# Atari_ST_4MB_RAM.net
KiCad netlist of a schematic drawn in EAGLE
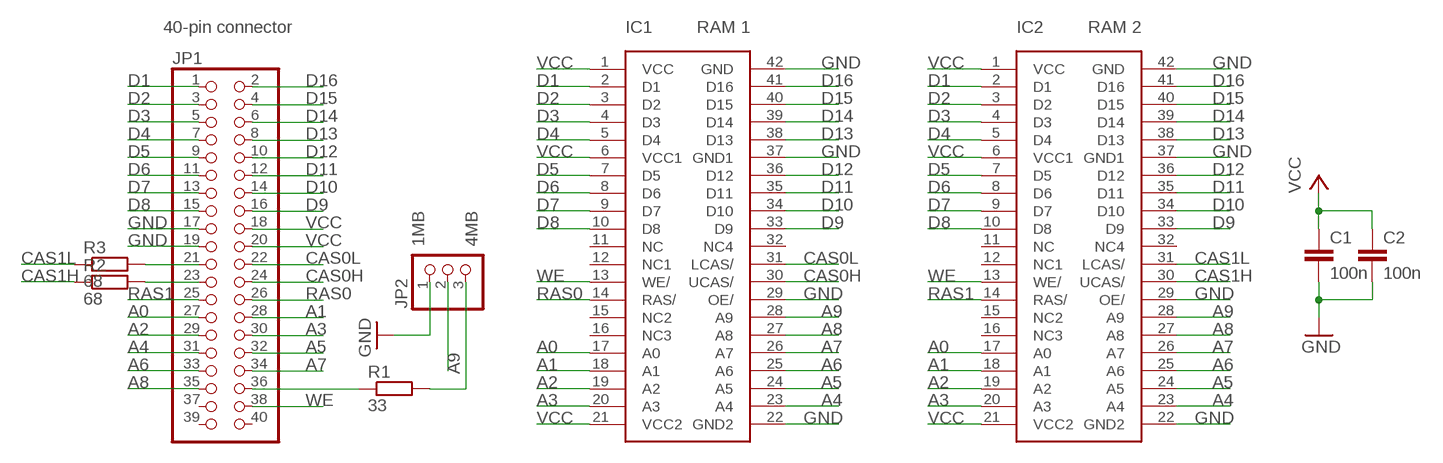
[diagram p0: schematic, sheet 1]

(export (version "E")
  (design (tool "Eeschema 10.0.6"))
  (components
    (comp (ref "C1")
      (value "100n")
      (footprint "eagle-import:C0805")
      (libsource (lib "eagle-import") (part "C-EUC0805"))
    )
    (comp (ref "C2")
      (value "100n")
      (footprint "eagle-import:C0805")
      (libsource (lib "eagle-import") (part "C-EUC0805"))
    )
    (comp (ref "IC1")
      (value "DRAMSOJ40A")
      (footprint "eagle-import:SOJ40")
      (libsource (lib "eagle-import") (part "DRAMSOJ40A"))
    )
    (comp (ref "IC2")
      (value "DRAMSOJ40A")
      (footprint "eagle-import:SOJ40")
      (libsource (lib "eagle-import") (part "DRAMSOJ40A"))
    )
    (comp (ref "JP1")
      (value "PINHD-2X20")
      (footprint "eagle-import:2X20")
      (libsource (lib "eagle-import") (part "PINHD-2X20"))
    )
    (comp (ref "JP2")
      (value "PINHD-1X3")
      (footprint "eagle-import:1X03")
      (libsource (lib "eagle-import") (part "PINHD-1X3"))
    )
    (comp (ref "R1")
      (value "33")
      (footprint "eagle-import:R0805")
      (libsource (lib "eagle-import") (part "R-EU_R0805"))
    )
    (comp (ref "R2")
      (value "68")
      (footprint "eagle-import:R0805")
      (libsource (lib "eagle-import") (part "R-EU_R0805"))
    )
    (comp (ref "R3")
      (value "68")
      (footprint "eagle-import:R0805")
      (libsource (lib "eagle-import") (part "R-EU_R0805"))
    )
  )
  (nets
    (net (code "1") (name "/A0") (class "Default")
      (node (ref "IC1") (pin "17") (pinfunction "A0_17") (pintype "input"))
      (node (ref "IC2") (pin "17") (pinfunction "A0_17") (pintype "input"))
      (node (ref "JP1") (pin "27") (pinfunction "27_27") (pintype "passive"))
    )
    (net (code "2") (name "/A1") (class "Default")
      (node (ref "IC1") (pin "18") (pinfunction "A1_18") (pintype "input"))
      (node (ref "IC2") (pin "18") (pinfunction "A1_18") (pintype "input"))
      (node (ref "JP1") (pin "28") (pinfunction "28_28") (pintype "passive"))
    )
    (net (code "3") (name "/A2") (class "Default")
      (node (ref "IC1") (pin "19") (pinfunction "A2_19") (pintype "input"))
      (node (ref "IC2") (pin "19") (pinfunction "A2_19") (pintype "input"))
      (node (ref "JP1") (pin "29") (pinfunction "29_29") (pintype "passive"))
    )
    (net (code "4") (name "/A3") (class "Default")
      (node (ref "IC1") (pin "20") (pinfunction "A3_20") (pintype "input"))
      (node (ref "IC2") (pin "20") (pinfunction "A3_20") (pintype "input"))
      (node (ref "JP1") (pin "30") (pinfunction "30_30") (pintype "passive"))
    )
    (net (code "5") (name "/A4") (class "Default")
      (node (ref "IC1") (pin "23") (pinfunction "A4_23") (pintype "input"))
      (node (ref "IC2") (pin "23") (pinfunction "A4_23") (pintype "input"))
      (node (ref "JP1") (pin "31") (pinfunction "31_31") (pintype "passive"))
    )
    (net (code "6") (name "/A5") (class "Default")
      (node (ref "IC1") (pin "24") (pinfunction "A5_24") (pintype "input"))
      (node (ref "IC2") (pin "24") (pinfunction "A5_24") (pintype "input"))
      (node (ref "JP1") (pin "32") (pinfunction "32_32") (pintype "passive"))
    )
    (net (code "7") (name "/A6") (class "Default")
      (node (ref "IC1") (pin "25") (pinfunction "A6_25") (pintype "input"))
      (node (ref "IC2") (pin "25") (pinfunction "A6_25") (pintype "input"))
      (node (ref "JP1") (pin "33") (pinfunction "33_33") (pintype "passive"))
    )
    (net (code "8") (name "/A7") (class "Default")
      (node (ref "IC1") (pin "26") (pinfunction "A7_26") (pintype "input"))
      (node (ref "IC2") (pin "26") (pinfunction "A7_26") (pintype "input"))
      (node (ref "JP1") (pin "34") (pinfunction "34_34") (pintype "passive"))
    )
    (net (code "9") (name "/A8") (class "Default")
      (node (ref "IC1") (pin "27") (pinfunction "A8_27") (pintype "input"))
      (node (ref "IC2") (pin "27") (pinfunction "A8_27") (pintype "input"))
      (node (ref "JP1") (pin "35") (pinfunction "35_35") (pintype "passive"))
    )
    (net (code "10") (name "/A9") (class "Default")
      (node (ref "IC1") (pin "28") (pinfunction "A9_28") (pintype "input"))
      (node (ref "IC2") (pin "28") (pinfunction "A9_28") (pintype "input"))
      (node (ref "JP2") (pin "2") (pinfunction "2_2") (pintype "passive"))
    )
    (net (code "11") (name "/CAS0H") (class "Default")
      (node (ref "IC1") (pin "30") (pinfunction "UCAS/_30") (pintype "bidirectional"))
      (node (ref "JP1") (pin "24") (pinfunction "24_24") (pintype "passive"))
    )
    (net (code "12") (name "/CAS0L") (class "Default")
      (node (ref "IC1") (pin "31") (pinfunction "LCAS/_31") (pintype "bidirectional"))
      (node (ref "JP1") (pin "22") (pinfunction "22_22") (pintype "passive"))
    )
    (net (code "13") (name "/CAS1H") (class "Default")
      (node (ref "IC2") (pin "30") (pinfunction "UCAS/_30") (pintype "bidirectional"))
      (node (ref "R2") (pin "1") (pinfunction "1_1") (pintype "passive"))
    )
    (net (code "14") (name "/CAS1L") (class "Default")
      (node (ref "IC2") (pin "31") (pinfunction "LCAS/_31") (pintype "bidirectional"))
      (node (ref "R3") (pin "1") (pinfunction "1_1") (pintype "passive"))
    )
    (net (code "15") (name "/D1") (class "Default")
      (node (ref "IC1") (pin "2") (pinfunction "D1_2") (pintype "tri_state"))
      (node (ref "IC2") (pin "2") (pinfunction "D1_2") (pintype "tri_state"))
      (node (ref "JP1") (pin "1") (pinfunction "1_1") (pintype "passive"))
    )
    (net (code "16") (name "/D2") (class "Default")
      (node (ref "IC1") (pin "3") (pinfunction "D2_3") (pintype "tri_state"))
      (node (ref "IC2") (pin "3") (pinfunction "D2_3") (pintype "tri_state"))
      (node (ref "JP1") (pin "3") (pinfunction "3_3") (pintype "passive"))
    )
    (net (code "17") (name "/D3") (class "Default")
      (node (ref "IC1") (pin "4") (pinfunction "D3_4") (pintype "tri_state"))
      (node (ref "IC2") (pin "4") (pinfunction "D3_4") (pintype "tri_state"))
      (node (ref "JP1") (pin "5") (pinfunction "5_5") (pintype "passive"))
    )
    (net (code "18") (name "/D4") (class "Default")
      (node (ref "IC1") (pin "5") (pinfunction "D4_5") (pintype "tri_state"))
      (node (ref "IC2") (pin "5") (pinfunction "D4_5") (pintype "tri_state"))
      (node (ref "JP1") (pin "7") (pinfunction "7_7") (pintype "passive"))
    )
    (net (code "19") (name "/D5") (class "Default")
      (node (ref "IC1") (pin "7") (pinfunction "D5_7") (pintype "tri_state"))
      (node (ref "IC2") (pin "7") (pinfunction "D5_7") (pintype "tri_state"))
      (node (ref "JP1") (pin "9") (pinfunction "9_9") (pintype "passive"))
    )
    (net (code "20") (name "/D6") (class "Default")
      (node (ref "IC1") (pin "8") (pinfunction "D6_8") (pintype "tri_state"))
      (node (ref "IC2") (pin "8") (pinfunction "D6_8") (pintype "tri_state"))
      (node (ref "JP1") (pin "11") (pinfunction "11_11") (pintype "passive"))
    )
    (net (code "21") (name "/D7") (class "Default")
      (node (ref "IC1") (pin "9") (pinfunction "D7_9") (pintype "tri_state"))
      (node (ref "IC2") (pin "9") (pinfunction "D7_9") (pintype "tri_state"))
      (node (ref "JP1") (pin "13") (pinfunction "13_13") (pintype "passive"))
    )
    (net (code "22") (name "/D8") (class "Default")
      (node (ref "IC1") (pin "10") (pinfunction "D8_10") (pintype "tri_state"))
      (node (ref "IC2") (pin "10") (pinfunction "D8_10") (pintype "tri_state"))
      (node (ref "JP1") (pin "15") (pinfunction "15_15") (pintype "passive"))
    )
    (net (code "23") (name "/D9") (class "Default")
      (node (ref "IC1") (pin "33") (pinfunction "D9_33") (pintype "input"))
      (node (ref "IC2") (pin "33") (pinfunction "D9_33") (pintype "input"))
      (node (ref "JP1") (pin "16") (pinfunction "16_16") (pintype "passive"))
    )
    (net (code "24") (name "/D10") (class "Default")
      (node (ref "IC1") (pin "34") (pinfunction "D10_34") (pintype "input"))
      (node (ref "IC2") (pin "34") (pinfunction "D10_34") (pintype "input"))
      (node (ref "JP1") (pin "14") (pinfunction "14_14") (pintype "passive"))
    )
    (net (code "25") (name "/D11") (class "Default")
      (node (ref "IC1") (pin "35") (pinfunction "D11_35") (pintype "input"))
      (node (ref "IC2") (pin "35") (pinfunction "D11_35") (pintype "input"))
      (node (ref "JP1") (pin "12") (pinfunction "12_12") (pintype "passive"))
    )
    (net (code "26") (name "/D12") (class "Default")
      (node (ref "IC1") (pin "36") (pinfunction "D12_36") (pintype "input"))
      (node (ref "IC2") (pin "36") (pinfunction "D12_36") (pintype "input"))
      (node (ref "JP1") (pin "10") (pinfunction "10_10") (pintype "passive"))
    )
    (net (code "27") (name "/D13") (class "Default")
      (node (ref "IC1") (pin "38") (pinfunction "D13_38") (pintype "input"))
      (node (ref "IC2") (pin "38") (pinfunction "D13_38") (pintype "input"))
      (node (ref "JP1") (pin "8") (pinfunction "8_8") (pintype "passive"))
    )
    (net (code "28") (name "/D14") (class "Default")
      (node (ref "IC1") (pin "39") (pinfunction "D14_39") (pintype "input"))
      (node (ref "IC2") (pin "39") (pinfunction "D14_39") (pintype "input"))
      (node (ref "JP1") (pin "6") (pinfunction "6_6") (pintype "passive"))
    )
    (net (code "29") (name "/D15") (class "Default")
      (node (ref "IC1") (pin "40") (pinfunction "D15_40") (pintype "input"))
      (node (ref "IC2") (pin "40") (pinfunction "D15_40") (pintype "input"))
      (node (ref "JP1") (pin "4") (pinfunction "4_4") (pintype "passive"))
    )
    (net (code "30") (name "/D16") (class "Default")
      (node (ref "IC1") (pin "41") (pinfunction "D16_41") (pintype "input"))
      (node (ref "IC2") (pin "41") (pinfunction "D16_41") (pintype "input"))
      (node (ref "JP1") (pin "2") (pinfunction "2_2") (pintype "passive"))
    )
    (net (code "31") (name "/RAS0") (class "Default")
      (node (ref "IC1") (pin "14") (pinfunction "RAS/_14") (pintype "input"))
      (node (ref "JP1") (pin "26") (pinfunction "26_26") (pintype "passive"))
    )
    (net (code "32") (name "/RAS1") (class "Default")
      (node (ref "IC2") (pin "14") (pinfunction "RAS/_14") (pintype "input"))
      (node (ref "JP1") (pin "25") (pinfunction "25_25") (pintype "passive"))
    )
    (net (code "33") (name "/WE") (class "Default")
      (node (ref "IC1") (pin "13") (pinfunction "WE/_13") (pintype "input"))
      (node (ref "IC2") (pin "13") (pinfunction "WE/_13") (pintype "input"))
      (node (ref "JP1") (pin "38") (pinfunction "38_38") (pintype "passive"))
    )
    (net (code "34") (name "GND") (class "Default")
      (node (ref "C1") (pin "2") (pinfunction "2_2") (pintype "passive"))
      (node (ref "C2") (pin "2") (pinfunction "2_2") (pintype "passive"))
      (node (ref "IC1") (pin "22") (pinfunction "GND2_22") (pintype "power_in"))
      (node (ref "IC1") (pin "29") (pinfunction "OE/_29") (pintype "input"))
      (node (ref "IC1") (pin "37") (pinfunction "GND1_37") (pintype "power_in"))
      (node (ref "IC1") (pin "42") (pinfunction "GND_42") (pintype "power_in"))
      (node (ref "IC2") (pin "22") (pinfunction "GND2_22") (pintype "power_in"))
      (node (ref "IC2") (pin "29") (pinfunction "OE/_29") (pintype "input"))
      (node (ref "IC2") (pin "37") (pinfunction "GND1_37") (pintype "power_in"))
      (node (ref "IC2") (pin "42") (pinfunction "GND_42") (pintype "power_in"))
      (node (ref "JP1") (pin "17") (pinfunction "17_17") (pintype "passive"))
      (node (ref "JP1") (pin "19") (pinfunction "19_19") (pintype "passive"))
      (node (ref "JP2") (pin "1") (pinfunction "1_1") (pintype "passive"))
    )
    (net (code "35") (name "Net-(JP1-Pad21)") (class "Default")
      (node (ref "JP1") (pin "21") (pinfunction "21_21") (pintype "passive"))
      (node (ref "R3") (pin "2") (pinfunction "2_2") (pintype "passive"))
    )
    (net (code "36") (name "Net-(JP1-Pad23)") (class "Default")
      (node (ref "JP1") (pin "23") (pinfunction "23_23") (pintype "passive"))
      (node (ref "R2") (pin "2") (pinfunction "2_2") (pintype "passive"))
    )
    (net (code "37") (name "Net-(JP1-Pad36)") (class "Default")
      (node (ref "JP1") (pin "36") (pinfunction "36_36") (pintype "passive"))
      (node (ref "R1") (pin "1") (pinfunction "1_1") (pintype "passive"))
    )
    (net (code "38") (name "Net-(JP2-Pad3)") (class "Default")
      (node (ref "JP2") (pin "3") (pinfunction "3_3") (pintype "passive"))
      (node (ref "R1") (pin "2") (pinfunction "2_2") (pintype "passive"))
    )
    (net (code "39") (name "VCC") (class "Default")
      (node (ref "C1") (pin "1") (pinfunction "1_1") (pintype "passive"))
      (node (ref "C2") (pin "1") (pinfunction "1_1") (pintype "passive"))
      (node (ref "IC1") (pin "1") (pinfunction "VCC_1") (pintype "power_in"))
      (node (ref "IC1") (pin "21") (pinfunction "VCC2_21") (pintype "power_in"))
      (node (ref "IC1") (pin "6") (pinfunction "VCC1_6") (pintype "power_in"))
      (node (ref "IC2") (pin "1") (pinfunction "VCC_1") (pintype "power_in"))
      (node (ref "IC2") (pin "21") (pinfunction "VCC2_21") (pintype "power_in"))
      (node (ref "IC2") (pin "6") (pinfunction "VCC1_6") (pintype "power_in"))
      (node (ref "JP1") (pin "18") (pinfunction "18_18") (pintype "passive"))
      (node (ref "JP1") (pin "20") (pinfunction "20_20") (pintype "passive"))
    )
    (net (code "40") (name "unconnected-(IC1-NC-Pad11)") (class "Default")
      (node (ref "IC1") (pin "11") (pinfunction "NC_11") (pintype "no_connect"))
    )
    (net (code "41") (name "unconnected-(IC1-NC1-Pad12)") (class "Default")
      (node (ref "IC1") (pin "12") (pinfunction "NC1_12") (pintype "no_connect"))
    )
    (net (code "42") (name "unconnected-(IC1-NC2-Pad15)") (class "Default")
      (node (ref "IC1") (pin "15") (pinfunction "NC2_15") (pintype "no_connect"))
    )
    (net (code "43") (name "unconnected-(IC1-NC3-Pad16)") (class "Default")
      (node (ref "IC1") (pin "16") (pinfunction "NC3_16") (pintype "no_connect"))
    )
    (net (code "44") (name "unconnected-(IC1-NC4-Pad32)") (class "Default")
      (node (ref "IC1") (pin "32") (pinfunction "NC4_32") (pintype "no_connect"))
    )
    (net (code "45") (name "unconnected-(IC2-NC-Pad11)") (class "Default")
      (node (ref "IC2") (pin "11") (pinfunction "NC_11") (pintype "no_connect"))
    )
    (net (code "46") (name "unconnected-(IC2-NC1-Pad12)") (class "Default")
      (node (ref "IC2") (pin "12") (pinfunction "NC1_12") (pintype "no_connect"))
    )
    (net (code "47") (name "unconnected-(IC2-NC2-Pad15)") (class "Default")
      (node (ref "IC2") (pin "15") (pinfunction "NC2_15") (pintype "no_connect"))
    )
    (net (code "48") (name "unconnected-(IC2-NC3-Pad16)") (class "Default")
      (node (ref "IC2") (pin "16") (pinfunction "NC3_16") (pintype "no_connect"))
    )
    (net (code "49") (name "unconnected-(IC2-NC4-Pad32)") (class "Default")
      (node (ref "IC2") (pin "32") (pinfunction "NC4_32") (pintype "no_connect"))
    )
    (net (code "50") (name "unconnected-(JP1-Pad37)") (class "Default")
      (node (ref "JP1") (pin "37") (pinfunction "37_37") (pintype "passive"))
    )
    (net (code "51") (name "unconnected-(JP1-Pad39)") (class "Default")
      (node (ref "JP1") (pin "39") (pinfunction "39_39") (pintype "passive"))
    )
    (net (code "52") (name "unconnected-(JP1-Pad40)") (class "Default")
      (node (ref "JP1") (pin "40") (pinfunction "40_40") (pintype "passive"))
    )
  )
)
